# ICM20602.net
KiCad netlist of a schematic drawn in EAGLE
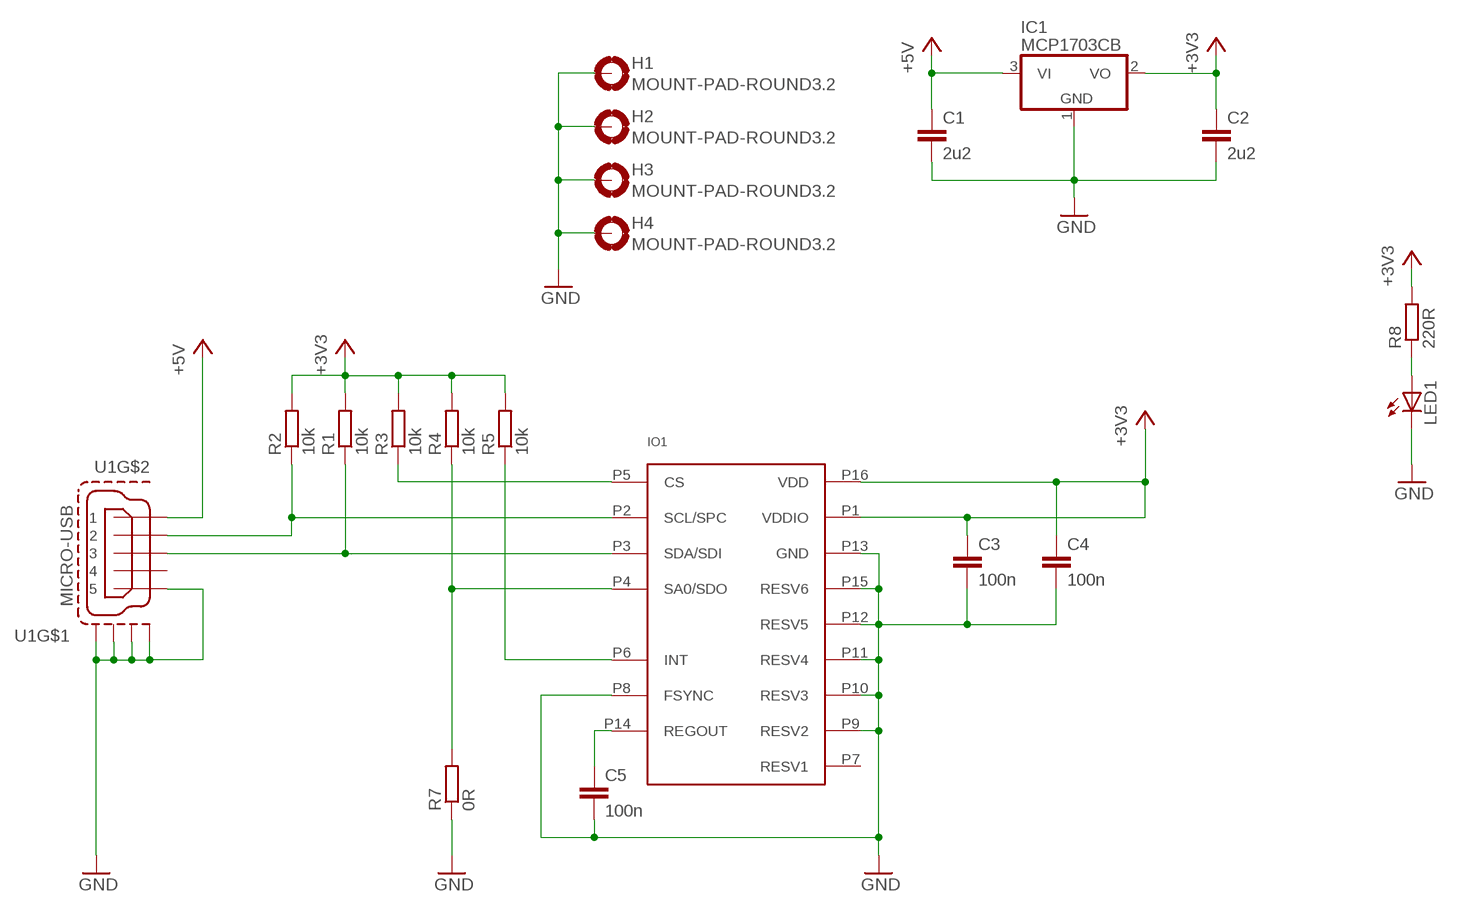
[diagram p0: schematic, sheet 1]

(export (version "E")
  (design (tool "Eeschema 10.0.6"))
  (components
    (comp (ref "C1")
      (value "2u2")
      (footprint "eagle-import:C0603")
      (libsource (lib "eagle-import") (part "C-EUC0603"))
    )
    (comp (ref "C2")
      (value "2u2")
      (footprint "eagle-import:C0603")
      (libsource (lib "eagle-import") (part "C-EUC0603"))
    )
    (comp (ref "C3")
      (value "100n")
      (footprint "eagle-import:C0603")
      (libsource (lib "eagle-import") (part "C-EUC0603"))
    )
    (comp (ref "C4")
      (value "100n")
      (footprint "eagle-import:C0603")
      (libsource (lib "eagle-import") (part "C-EUC0603"))
    )
    (comp (ref "C5")
      (value "100n")
      (footprint "eagle-import:C0603")
      (libsource (lib "eagle-import") (part "C-EUC0603"))
    )
    (comp (ref "H1")
      (value "MOUNT-PAD-ROUND3.2")
      (footprint "eagle-import:3,2-PAD")
      (libsource (lib "eagle-import") (part "MOUNT-PAD-ROUND3.2"))
    )
    (comp (ref "H2")
      (value "MOUNT-PAD-ROUND3.2")
      (footprint "eagle-import:3,2-PAD")
      (libsource (lib "eagle-import") (part "MOUNT-PAD-ROUND3.2"))
    )
    (comp (ref "H3")
      (value "MOUNT-PAD-ROUND3.2")
      (footprint "eagle-import:3,2-PAD")
      (libsource (lib "eagle-import") (part "MOUNT-PAD-ROUND3.2"))
    )
    (comp (ref "H4")
      (value "MOUNT-PAD-ROUND3.2")
      (footprint "eagle-import:3,2-PAD")
      (libsource (lib "eagle-import") (part "MOUNT-PAD-ROUND3.2"))
    )
    (comp (ref "IC1")
      (value "MCP1703CB")
      (footprint "eagle-import:SOT23")
      (libsource (lib "eagle-import") (part "MCP1703CB"))
    )
    (comp (ref "IO1")
      (value "ICM20602")
      (footprint "eagle-import:LGA16")
      (libsource (lib "eagle-import") (part "ICM20602"))
    )
    (comp (ref "LED1")
      (value "LEDSML0603")
      (footprint "eagle-import:SML0603")
      (libsource (lib "eagle-import") (part "LEDSML0603"))
    )
    (comp (ref "R1")
      (value "10k")
      (footprint "eagle-import:R0603")
      (libsource (lib "eagle-import") (part "R-EU_R0603"))
    )
    (comp (ref "R2")
      (value "10k")
      (footprint "eagle-import:R0603")
      (libsource (lib "eagle-import") (part "R-EU_R0603"))
    )
    (comp (ref "R3")
      (value "10k")
      (footprint "eagle-import:R0603")
      (libsource (lib "eagle-import") (part "R-EU_R0603"))
    )
    (comp (ref "R4")
      (value "10k")
      (footprint "eagle-import:R0603")
      (libsource (lib "eagle-import") (part "R-EU_R0603"))
    )
    (comp (ref "R5")
      (value "10k")
      (footprint "eagle-import:R0603")
      (libsource (lib "eagle-import") (part "R-EU_R0603"))
    )
    (comp (ref "R7")
      (value "0R")
      (footprint "eagle-import:R0603")
      (libsource (lib "eagle-import") (part "R-EU_R0603"))
    )
    (comp (ref "R8")
      (value "220R")
      (footprint "eagle-import:R0603")
      (libsource (lib "eagle-import") (part "R-EU_R0603"))
    )
    (comp (ref "U1")
      (value "MICRO-USB")
      (footprint "eagle-import:ZX62R-B-5P")
      (libsource (lib "eagle-import") (part "MICRO-USB-SHIELD-ZX62R-B-5P"))
    )
  )
  (nets
    (net (code "1") (name "+3V3") (class "Default")
      (node (ref "C2") (pin "1") (pinfunction "1_1") (pintype "passive"))
      (node (ref "C3") (pin "1") (pinfunction "1_1") (pintype "passive"))
      (node (ref "C4") (pin "1") (pinfunction "1_1") (pintype "passive"))
      (node (ref "IC1") (pin "2") (pinfunction "VO_2") (pintype "passive"))
      (node (ref "IO1") (pin "P1") (pinfunction "VDDIO_P1") (pintype "power_in"))
      (node (ref "IO1") (pin "P16") (pinfunction "VDD_P16") (pintype "power_in"))
      (node (ref "R1") (pin "2") (pinfunction "2_2") (pintype "passive"))
      (node (ref "R2") (pin "2") (pinfunction "2_2") (pintype "passive"))
      (node (ref "R3") (pin "2") (pinfunction "2_2") (pintype "passive"))
      (node (ref "R4") (pin "2") (pinfunction "2_2") (pintype "passive"))
      (node (ref "R5") (pin "2") (pinfunction "2_2") (pintype "passive"))
      (node (ref "R8") (pin "2") (pinfunction "2_2") (pintype "passive"))
    )
    (net (code "2") (name "+5V") (class "Default")
      (node (ref "C1") (pin "1") (pinfunction "1_1") (pintype "passive"))
      (node (ref "IC1") (pin "3") (pinfunction "VI_3") (pintype "input"))
      (node (ref "U1") (pin "1") (pinfunction "1_1") (pintype "input"))
    )
    (net (code "3") (name "GND") (class "Default")
      (node (ref "C1") (pin "2") (pinfunction "2_2") (pintype "passive"))
      (node (ref "C2") (pin "2") (pinfunction "2_2") (pintype "passive"))
      (node (ref "C3") (pin "2") (pinfunction "2_2") (pintype "passive"))
      (node (ref "C4") (pin "2") (pinfunction "2_2") (pintype "passive"))
      (node (ref "C5") (pin "2") (pinfunction "2_2") (pintype "passive"))
      (node (ref "H1") (pin "B3,2") (pinfunction "MOUNT_B3,2") (pintype "passive"))
      (node (ref "H2") (pin "B3,2") (pinfunction "MOUNT_B3,2") (pintype "passive"))
      (node (ref "H3") (pin "B3,2") (pinfunction "MOUNT_B3,2") (pintype "passive"))
      (node (ref "H4") (pin "B3,2") (pinfunction "MOUNT_B3,2") (pintype "passive"))
      (node (ref "IC1") (pin "1") (pinfunction "GND_1") (pintype "passive"))
      (node (ref "IO1") (pin "P10") (pinfunction "RESV3_P10") (pintype "passive"))
      (node (ref "IO1") (pin "P11") (pinfunction "RESV4_P11") (pintype "passive"))
      (node (ref "IO1") (pin "P12") (pinfunction "RESV5_P12") (pintype "passive"))
      (node (ref "IO1") (pin "P13") (pinfunction "GND_P13") (pintype "power_in"))
      (node (ref "IO1") (pin "P15") (pinfunction "RESV6_P15") (pintype "passive"))
      (node (ref "IO1") (pin "P8") (pinfunction "FSYNC_P8") (pintype "input"))
      (node (ref "IO1") (pin "P9") (pinfunction "RESV2_P9") (pintype "passive"))
      (node (ref "LED1") (pin "C") (pinfunction "C_C") (pintype "passive"))
      (node (ref "R7") (pin "1") (pinfunction "1_1") (pintype "passive"))
      (node (ref "U1") (pin "5") (pinfunction "5_5") (pintype "input"))
      (node (ref "U1") (pin "M1") (pinfunction "S1_M1") (pintype "passive"))
      (node (ref "U1") (pin "M2") (pinfunction "S2_M2") (pintype "passive"))
      (node (ref "U1") (pin "M3") (pinfunction "S3_M3") (pintype "passive"))
      (node (ref "U1") (pin "M4") (pinfunction "S4_M4") (pintype "passive"))
    )
    (net (code "4") (name "Net-(IO1-CS)") (class "Default")
      (node (ref "IO1") (pin "P5") (pinfunction "CS_P5") (pintype "input"))
      (node (ref "R3") (pin "1") (pinfunction "1_1") (pintype "passive"))
    )
    (net (code "5") (name "Net-(IO1-INT)") (class "Default")
      (node (ref "IO1") (pin "P6") (pinfunction "INT_P6") (pintype "output"))
      (node (ref "R5") (pin "1") (pinfunction "1_1") (pintype "passive"))
    )
    (net (code "6") (name "Net-(IO1-REGOUT)") (class "Default")
      (node (ref "C5") (pin "1") (pinfunction "1_1") (pintype "passive"))
      (node (ref "IO1") (pin "P14") (pinfunction "REGOUT_P14") (pintype "output"))
    )
    (net (code "7") (name "Net-(IO1-SA0{slash}SDO)") (class "Default")
      (node (ref "IO1") (pin "P4") (pinfunction "SA0/SDO_P4") (pintype "input"))
      (node (ref "R4") (pin "1") (pinfunction "1_1") (pintype "passive"))
      (node (ref "R7") (pin "2") (pinfunction "2_2") (pintype "passive"))
    )
    (net (code "8") (name "Net-(IO1-SCL{slash}SPC)") (class "Default")
      (node (ref "IO1") (pin "P2") (pinfunction "SCL/SPC_P2") (pintype "input"))
      (node (ref "R2") (pin "1") (pinfunction "1_1") (pintype "passive"))
      (node (ref "U1") (pin "2") (pinfunction "2_2") (pintype "input"))
    )
    (net (code "9") (name "Net-(IO1-SDA{slash}SDI)") (class "Default")
      (node (ref "IO1") (pin "P3") (pinfunction "SDA/SDI_P3") (pintype "bidirectional"))
      (node (ref "R1") (pin "1") (pinfunction "1_1") (pintype "passive"))
      (node (ref "U1") (pin "3") (pinfunction "3_3") (pintype "input"))
    )
    (net (code "10") (name "Net-(LED1-PadA)") (class "Default")
      (node (ref "LED1") (pin "A") (pinfunction "A_A") (pintype "passive"))
      (node (ref "R8") (pin "1") (pinfunction "1_1") (pintype "passive"))
    )
    (net (code "11") (name "unconnected-(IO1-RESV1-PadP7)") (class "Default")
      (node (ref "IO1") (pin "P7") (pinfunction "RESV1_P7") (pintype "passive"))
    )
    (net (code "12") (name "unconnected-(U1-Pad4)") (class "Default")
      (node (ref "U1") (pin "4") (pinfunction "4_4") (pintype "input"))
    )
  )
)
